# ESP32.net
KiCad netlist of a schematic drawn in Altium Designer
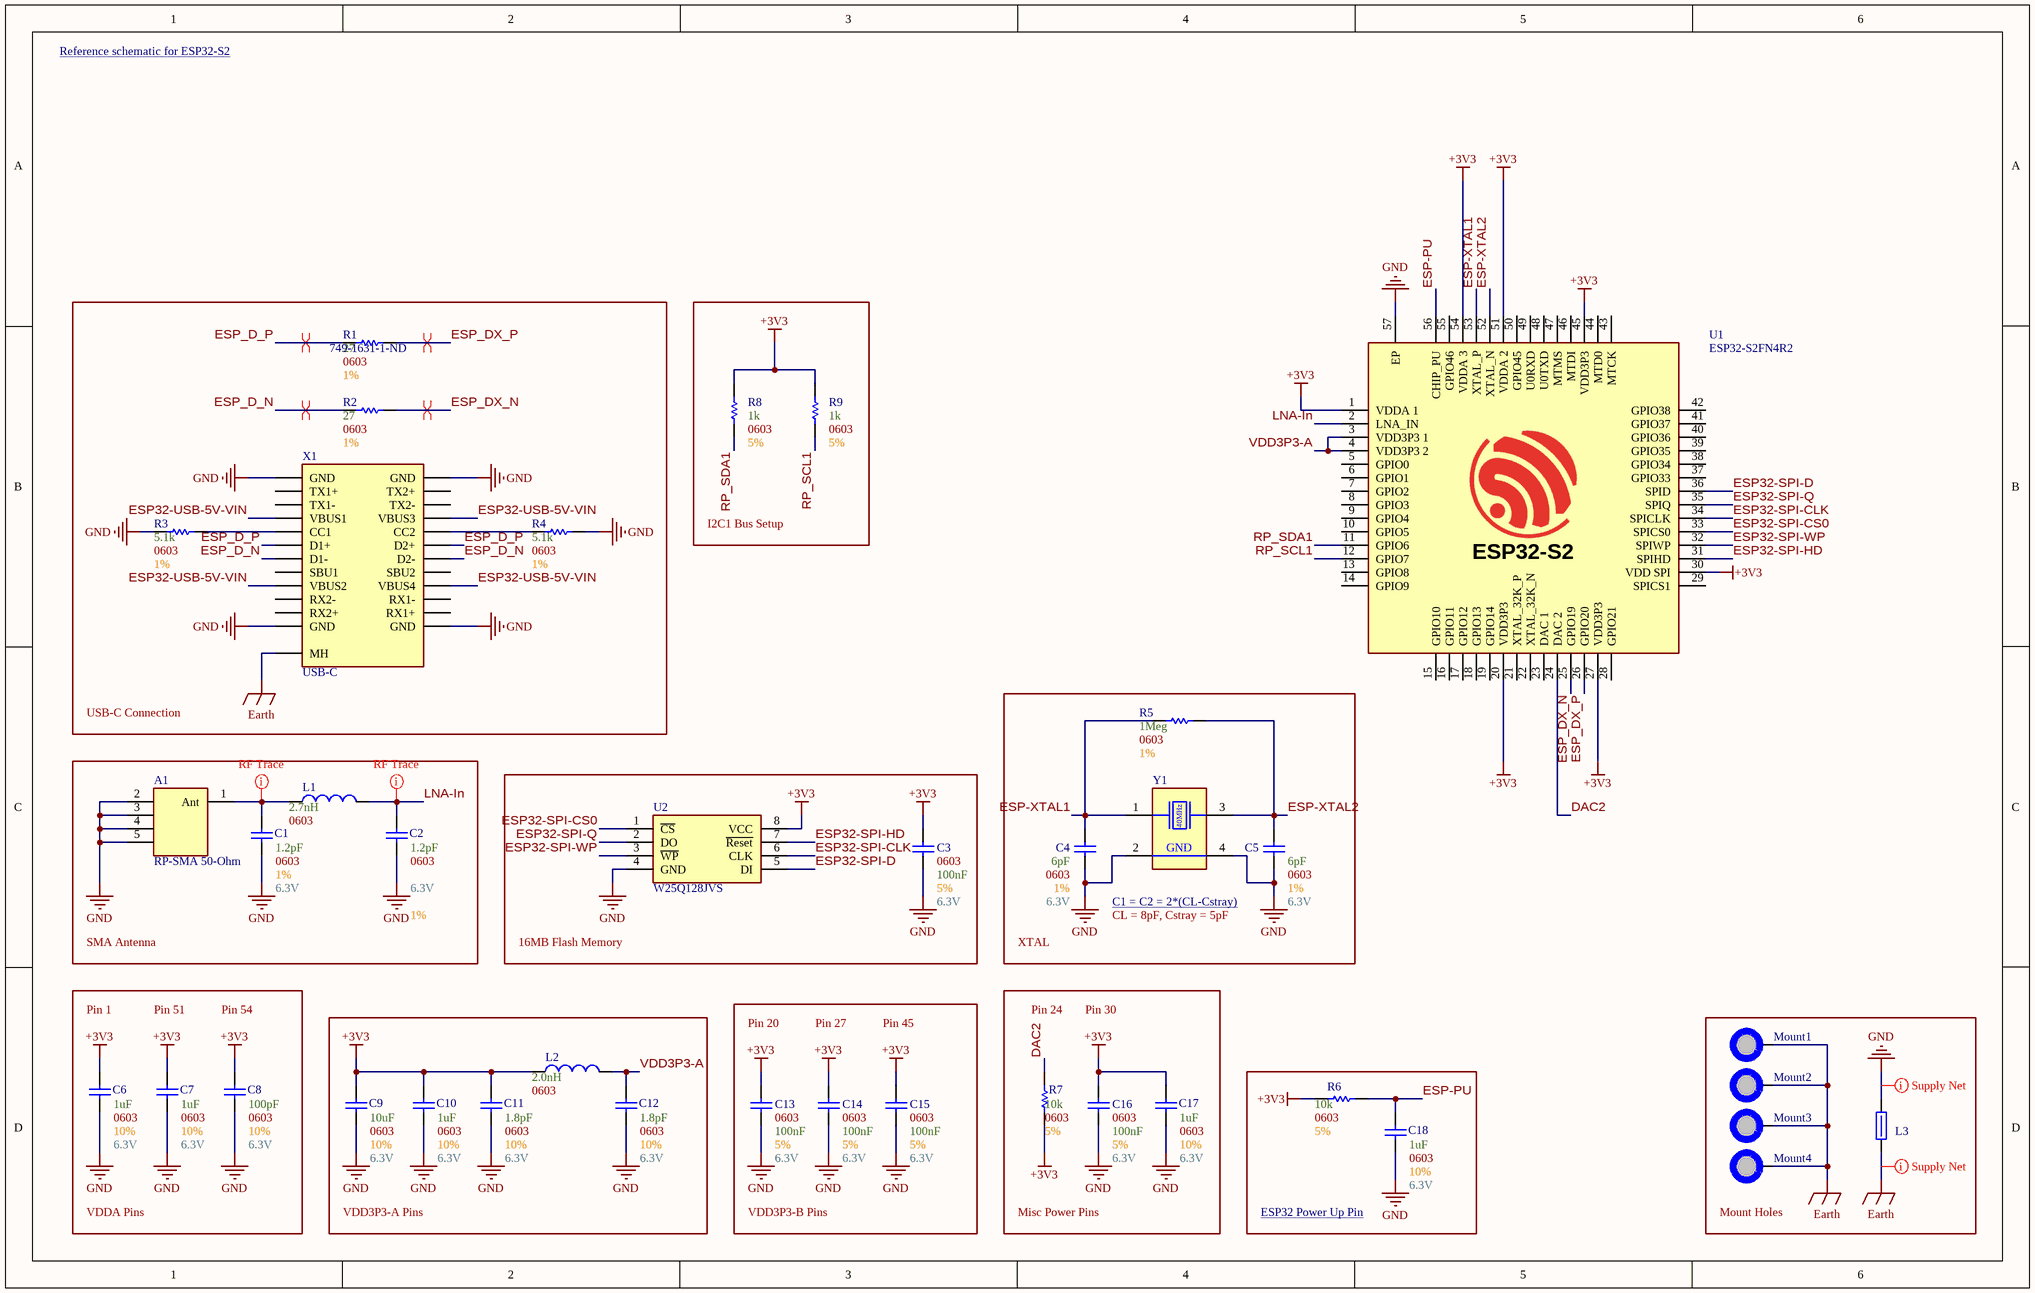
[diagram p0: ESP32.SchDoc]

(export (version "E")
  (design (tool "Eeschema 10.0.6"))
  (components
    (comp (ref "A1")
      (value "RP-SMA 50-Ohm")
      (footprint "[SMA] RP-SMA 90deg Jack")
      (description "PCB.RPSMAFRA.HT")
      (libsource (lib "RADM Connectors") (part "[SMA] RP-SMA 90deg Jack"))
    )
    (comp (ref "C1")
      (value "SMD Nonpolarized")
      (footprint "[Cap] SMD 0603")
      (fields
        (field (name "VOLTAGE") "6.3V")
        (field (name "TOLERANCE") "1%")
        (field (name "SIZE PACKAGE") "0603")
        (field (name "CAPACITANCE") "1.2pF")
      )
      (libsource (lib "RADM Components") (part "[Cap] SMD Nonpolarized"))
    )
    (comp (ref "C2")
      (value "SMD Nonpolarized")
      (footprint "[Cap] SMD 0603")
      (fields
        (field (name "VOLTAGE") "6.3V")
        (field (name "TOLERANCE") "1%")
        (field (name "SIZE PACKAGE") "0603")
        (field (name "CAPACITANCE") "1.2pF")
      )
      (libsource (lib "RADM Components") (part "[Cap] SMD Nonpolarized"))
    )
    (comp (ref "C3")
      (value "[Cap] SMD Nonpolarized")
      (footprint "[Cap] SMD 0603")
      (fields
        (field (name "SIZE PACKAGE") "0603")
        (field (name "CAPACITANCE") "100nF")
        (field (name "VOLTAGE") "6.3V")
        (field (name "TOLERANCE") "5%")
      )
      (libsource (lib "RADM Components") (part "[Cap] SMD Nonpolarized"))
    )
    (comp (ref "C4")
      (value "SMD Nonpolarized")
      (footprint "[Cap] SMD 0603")
      (fields
        (field (name "VOLTAGE") "6.3V")
        (field (name "TOLERANCE") "1%")
        (field (name "SIZE PACKAGE") "0603")
        (field (name "CAPACITANCE") "6pF")
      )
      (libsource (lib "RADM Components") (part "[Cap] SMD Nonpolarized"))
    )
    (comp (ref "C5")
      (value "SMD Nonpolarized")
      (footprint "[Cap] SMD 0603")
      (fields
        (field (name "VOLTAGE") "6.3V")
        (field (name "TOLERANCE") "1%")
        (field (name "SIZE PACKAGE") "0603")
        (field (name "CAPACITANCE") "6pF")
      )
      (libsource (lib "RADM Components") (part "[Cap] SMD Nonpolarized"))
    )
    (comp (ref "C6")
      (value "SMD Nonpolarized")
      (footprint "[Cap] SMD 0603")
      (fields
        (field (name "VOLTAGE") "6.3V")
        (field (name "TOLERANCE") "10%")
        (field (name "SIZE PACKAGE") "0603")
        (field (name "CAPACITANCE") "1uF")
      )
      (libsource (lib "RADM Components") (part "[Cap] SMD Nonpolarized"))
    )
    (comp (ref "C7")
      (value "SMD Nonpolarized")
      (footprint "[Cap] SMD 0603")
      (fields
        (field (name "VOLTAGE") "6.3V")
        (field (name "TOLERANCE") "10%")
        (field (name "SIZE PACKAGE") "0603")
        (field (name "CAPACITANCE") "1uF")
      )
      (libsource (lib "RADM Components") (part "[Cap] SMD Nonpolarized"))
    )
    (comp (ref "C8")
      (value "SMD Nonpolarized")
      (footprint "[Cap] SMD 0603")
      (fields
        (field (name "VOLTAGE") "6.3V")
        (field (name "TOLERANCE") "10%")
        (field (name "SIZE PACKAGE") "0603")
        (field (name "CAPACITANCE") "100pF")
      )
      (libsource (lib "RADM Components") (part "[Cap] SMD Nonpolarized"))
    )
    (comp (ref "C9")
      (value "SMD Nonpolarized")
      (footprint "[Cap] SMD 0603")
      (fields
        (field (name "VOLTAGE") "6.3V")
        (field (name "TOLERANCE") "10%")
        (field (name "SIZE PACKAGE") "0603")
        (field (name "CAPACITANCE") "10uF")
      )
      (libsource (lib "RADM Components") (part "[Cap] SMD Nonpolarized"))
    )
    (comp (ref "C10")
      (value "SMD Nonpolarized")
      (footprint "[Cap] SMD 0603")
      (fields
        (field (name "VOLTAGE") "6.3V")
        (field (name "TOLERANCE") "10%")
        (field (name "SIZE PACKAGE") "0603")
        (field (name "CAPACITANCE") "1uF")
      )
      (libsource (lib "RADM Components") (part "[Cap] SMD Nonpolarized"))
    )
    (comp (ref "C11")
      (value "SMD Nonpolarized")
      (footprint "[Cap] SMD 0603")
      (fields
        (field (name "VOLTAGE") "6.3V")
        (field (name "TOLERANCE") "10%")
        (field (name "SIZE PACKAGE") "0603")
        (field (name "CAPACITANCE") "1.8pF")
      )
      (libsource (lib "RADM Components") (part "[Cap] SMD Nonpolarized"))
    )
    (comp (ref "C12")
      (value "SMD Nonpolarized")
      (footprint "[Cap] SMD 0603")
      (fields
        (field (name "VOLTAGE") "6.3V")
        (field (name "TOLERANCE") "10%")
        (field (name "SIZE PACKAGE") "0603")
        (field (name "CAPACITANCE") "1.8pF")
      )
      (libsource (lib "RADM Components") (part "[Cap] SMD Nonpolarized"))
    )
    (comp (ref "C13")
      (value "[Cap] SMD Nonpolarized")
      (footprint "[Cap] SMD 0603")
      (fields
        (field (name "SIZE PACKAGE") "0603")
        (field (name "CAPACITANCE") "100nF")
        (field (name "VOLTAGE") "6.3V")
        (field (name "TOLERANCE") "5%")
      )
      (libsource (lib "RADM Components") (part "[Cap] SMD Nonpolarized"))
    )
    (comp (ref "C14")
      (value "[Cap] SMD Nonpolarized")
      (footprint "[Cap] SMD 0603")
      (fields
        (field (name "SIZE PACKAGE") "0603")
        (field (name "CAPACITANCE") "100nF")
        (field (name "VOLTAGE") "6.3V")
        (field (name "TOLERANCE") "5%")
      )
      (libsource (lib "RADM Components") (part "[Cap] SMD Nonpolarized"))
    )
    (comp (ref "C15")
      (value "[Cap] SMD Nonpolarized")
      (footprint "[Cap] SMD 0603")
      (fields
        (field (name "SIZE PACKAGE") "0603")
        (field (name "CAPACITANCE") "100nF")
        (field (name "VOLTAGE") "6.3V")
        (field (name "TOLERANCE") "5%")
      )
      (libsource (lib "RADM Components") (part "[Cap] SMD Nonpolarized"))
    )
    (comp (ref "C16")
      (value "[Cap] SMD Nonpolarized")
      (footprint "[Cap] SMD 0603")
      (fields
        (field (name "SIZE PACKAGE") "0603")
        (field (name "CAPACITANCE") "100nF")
        (field (name "VOLTAGE") "6.3V")
        (field (name "TOLERANCE") "5%")
      )
      (libsource (lib "RADM Components") (part "[Cap] SMD Nonpolarized"))
    )
    (comp (ref "C17")
      (value "SMD Nonpolarized")
      (footprint "[Cap] SMD 0603")
      (fields
        (field (name "VOLTAGE") "6.3V")
        (field (name "TOLERANCE") "10%")
        (field (name "SIZE PACKAGE") "0603")
        (field (name "CAPACITANCE") "1uF")
      )
      (libsource (lib "RADM Components") (part "[Cap] SMD Nonpolarized"))
    )
    (comp (ref "C18")
      (value "SMD Nonpolarized")
      (footprint "[Cap] SMD 0603")
      (fields
        (field (name "VOLTAGE") "6.3V")
        (field (name "TOLERANCE") "10%")
        (field (name "SIZE PACKAGE") "0603")
        (field (name "CAPACITANCE") "1uF")
      )
      (libsource (lib "RADM Components") (part "[Cap] SMD Nonpolarized"))
    )
    (comp (ref "L1")
      (value "SMD Inductor")
      (footprint "[Inductor] SMD 0603")
      (fields (field (name "SIZE PACKAGE") "0603") (field (name "INDUCTANCE") "2.7nH"))
      (libsource (lib "RADM Components") (part "[Inductor] SMD Inductor"))
    )
    (comp (ref "L2")
      (value "SMD Inductor")
      (footprint "[Inductor] SMD 0603")
      (fields (field (name "SIZE PACKAGE") "0603") (field (name "INDUCTANCE") "2.0nH"))
      (libsource (lib "RADM Components") (part "[Inductor] SMD Inductor"))
    )
    (comp (ref "L3")
      (value "652-MH2029-300Y")
      (footprint "[Ferrite] SMD Bead 0805 (1)")
      (libsource (lib "RADM Components") (part "[Ferrite] SMD Ferrite Bead (1)"))
    )
    (comp (ref "Mount1")
      (value "M3 Mount Hole")
      (footprint "[Mount] M3 Mount Hole")
      (description "Place at least 4.5mm from board edge. Plated.")
      (libsource (lib "RADM Connectors") (part "[Mount] M3 Mount Hole"))
    )
    (comp (ref "Mount2")
      (value "M3 Mount Hole")
      (footprint "[Mount] M3 Mount Hole")
      (description "Place at least 4.5mm from board edge. Plated.")
      (libsource (lib "RADM Connectors") (part "[Mount] M3 Mount Hole"))
    )
    (comp (ref "Mount3")
      (value "M3 Mount Hole")
      (footprint "[Mount] M3 Mount Hole")
      (description "Place at least 4.5mm from board edge. Plated.")
      (libsource (lib "RADM Connectors") (part "[Mount] M3 Mount Hole"))
    )
    (comp (ref "Mount4")
      (value "M3 Mount Hole")
      (footprint "[Mount] M3 Mount Hole")
      (description "Place at least 4.5mm from board edge. Plated.")
      (libsource (lib "RADM Connectors") (part "[Mount] M3 Mount Hole"))
    )
    (comp (ref "R1")
      (value "[Res] SMD Resistor")
      (footprint "[Res] SMD 0603")
      (description "Generic")
      (fields
        (field (name "TOLERANCE") "1%")
        (field (name "RESISTANCE") "27")
        (field (name "SIZE PACKAGE") "0603")
        (field (name "SUPPLIER PART NUMBER 1") "749-1631-1-ND")
      )
      (libsource (lib "RADM Components") (part "[Res] SMD Resistor"))
    )
    (comp (ref "R2")
      (value "[Res] SMD Resistor")
      (footprint "[Res] SMD 0603")
      (description "Generic")
      (fields
        (field (name "TOLERANCE") "1%")
        (field (name "RESISTANCE") "27")
        (field (name "SIZE PACKAGE") "0603")
      )
      (libsource (lib "RADM Components") (part "[Res] SMD Resistor"))
    )
    (comp (ref "R3")
      (value "[Res] SMD Resistor")
      (footprint "[Res] SMD 0603")
      (description "Generic")
      (fields
        (field (name "TOLERANCE") "1%")
        (field (name "RESISTANCE") "5.1k")
        (field (name "SIZE PACKAGE") "0603")
      )
      (libsource (lib "RADM Components") (part "[Res] SMD Resistor"))
    )
    (comp (ref "R4")
      (value "[Res] SMD Resistor")
      (footprint "[Res] SMD 0603")
      (description "Generic")
      (fields
        (field (name "TOLERANCE") "1%")
        (field (name "RESISTANCE") "5.1k")
        (field (name "SIZE PACKAGE") "0603")
      )
      (libsource (lib "RADM Components") (part "[Res] SMD Resistor"))
    )
    (comp (ref "R5")
      (value "[Res] SMD Resistor")
      (footprint "[Res] SMD 0603")
      (description "Generic")
      (fields
        (field (name "TOLERANCE") "1%")
        (field (name "RESISTANCE") "1Meg")
        (field (name "SIZE PACKAGE") "0603")
      )
      (libsource (lib "RADM Components") (part "[Res] SMD Resistor"))
    )
    (comp (ref "R6")
      (value "[Res] SMD Resistor")
      (footprint "[Res] SMD 0603")
      (description "Generic")
      (fields
        (field (name "TOLERANCE") "5%")
        (field (name "RESISTANCE") "10k")
        (field (name "SIZE PACKAGE") "0603")
      )
      (libsource (lib "RADM Components") (part "[Res] SMD Resistor"))
    )
    (comp (ref "R7")
      (value "[Res] SMD Resistor")
      (footprint "[Res] SMD 0603")
      (description "Generic")
      (fields
        (field (name "TOLERANCE") "5%")
        (field (name "RESISTANCE") "10k")
        (field (name "SIZE PACKAGE") "0603")
      )
      (libsource (lib "RADM Components") (part "[Res] SMD Resistor"))
    )
    (comp (ref "R8")
      (value "[Res] SMD Resistor")
      (footprint "[Res] SMD 0603")
      (description "Generic")
      (fields
        (field (name "RESISTANCE") "1k")
        (field (name "SIZE PACKAGE") "0603")
        (field (name "TOLERANCE") "5%")
      )
      (libsource (lib "RADM Components") (part "[Res] SMD Resistor"))
    )
    (comp (ref "R9")
      (value "[Res] SMD Resistor")
      (footprint "[Res] SMD 0603")
      (description "Generic")
      (fields
        (field (name "RESISTANCE") "1k")
        (field (name "SIZE PACKAGE") "0603")
        (field (name "TOLERANCE") "5%")
      )
      (libsource (lib "RADM Components") (part "[Res] SMD Resistor"))
    )
    (comp (ref "U1")
      (value "ESP32-S2FN4R2")
      (footprint "[MCU] ESP32-S2")
      (libsource (lib "RADM Components") (part "[MCU] ESP32-S2"))
    )
    (comp (ref "U2")
      (value "W25Q128JVS")
      (footprint "[Mem] 16Mb Flash Memory")
      (description "W25Q128JVSIQ TR")
      (libsource (lib "RADM Components") (part "[Mem] 16Mb Flash Memory"))
    )
    (comp (ref "X1")
      (value "USB-C")
      (footprint "[Port] USB-C")
      (libsource (lib "RADM Connectors") (part "[Port] USB Type-C"))
    )
    (comp (ref "Y1")
      (value "40MHz Crystal")
      (footprint "[XTAL] SMD 40MHz")
      (description "CX2016DB40000D0FLJCC")
      (libsource (lib "RADM Components") (part "[XTAL] SMD 40MHz"))
    )
  )
  (nets
    (net (code "1") (name "+3V3") (class "Default")
      (node (ref "C10") (pin "2") (pinfunction "2_2") (pintype "passive"))
      (node (ref "C11") (pin "2") (pinfunction "2_2") (pintype "passive"))
      (node (ref "C13") (pin "2") (pinfunction "2_2") (pintype "passive"))
      (node (ref "C14") (pin "2") (pinfunction "2_2") (pintype "passive"))
      (node (ref "C15") (pin "2") (pinfunction "2_2") (pintype "passive"))
      (node (ref "C16") (pin "2") (pinfunction "2_2") (pintype "passive"))
      (node (ref "C17") (pin "2") (pinfunction "2_2") (pintype "passive"))
      (node (ref "C3") (pin "2") (pinfunction "2_2") (pintype "passive"))
      (node (ref "C6") (pin "2") (pinfunction "2_2") (pintype "passive"))
      (node (ref "C7") (pin "2") (pinfunction "2_2") (pintype "passive"))
      (node (ref "C8") (pin "2") (pinfunction "2_2") (pintype "passive"))
      (node (ref "C9") (pin "2") (pinfunction "2_2") (pintype "passive"))
      (node (ref "L2") (pin "1") (pinfunction "1_1") (pintype "passive"))
      (node (ref "R6") (pin "1") (pinfunction "1_1") (pintype "passive"))
      (node (ref "R7") (pin "1") (pinfunction "1_1") (pintype "passive"))
      (node (ref "R8") (pin "2") (pinfunction "2_2") (pintype "passive"))
      (node (ref "R9") (pin "2") (pinfunction "2_2") (pintype "passive"))
      (node (ref "U1") (pin "1") (pinfunction "VDDA_1_1") (pintype "passive"))
      (node (ref "U1") (pin "20") (pinfunction "VDD3P3_20") (pintype "passive"))
      (node (ref "U1") (pin "27") (pinfunction "VDD3P3_27") (pintype "passive"))
      (node (ref "U1") (pin "30") (pinfunction "VDD_SPI_30") (pintype "passive"))
      (node (ref "U1") (pin "45") (pinfunction "VDD3P3_45") (pintype "passive"))
      (node (ref "U1") (pin "51") (pinfunction "VDDA_2_51") (pintype "passive"))
      (node (ref "U1") (pin "54") (pinfunction "VDDA_3_54") (pintype "passive"))
      (node (ref "U2") (pin "8") (pinfunction "VCC_8") (pintype "passive"))
    )
    (net (code "2") (name "/DAC2") (class "Default")
      (node (ref "R7") (pin "2") (pinfunction "2_2") (pintype "passive"))
      (node (ref "U1") (pin "24") (pinfunction "DAC_2_24") (pintype "passive"))
    )
    (net (code "3") (name "/ESP-PU") (class "Default")
      (node (ref "C18") (pin "2") (pinfunction "2_2") (pintype "passive"))
      (node (ref "R6") (pin "2") (pinfunction "2_2") (pintype "passive"))
      (node (ref "U1") (pin "56") (pinfunction "CHIP_PU_56") (pintype "passive"))
    )
    (net (code "4") (name "/ESP-XTAL1") (class "Default")
      (node (ref "C4") (pin "2") (pinfunction "2_2") (pintype "passive"))
      (node (ref "R5") (pin "2") (pinfunction "2_2") (pintype "passive"))
      (node (ref "U1") (pin "53") (pinfunction "XTAL_P_53") (pintype "passive"))
      (node (ref "Y1") (pin "1") (pinfunction "XTAL1_1") (pintype "power_in"))
    )
    (net (code "5") (name "/ESP-XTAL2") (class "Default")
      (node (ref "C5") (pin "2") (pinfunction "2_2") (pintype "passive"))
      (node (ref "R5") (pin "1") (pinfunction "1_1") (pintype "passive"))
      (node (ref "U1") (pin "52") (pinfunction "XTAL_N_52") (pintype "passive"))
      (node (ref "Y1") (pin "3") (pinfunction "XTAL2_3") (pintype "power_in"))
    )
    (net (code "6") (name "/ESP32-SPI-CLK") (class "Default")
      (node (ref "U1") (pin "34") (pinfunction "SPICLK_34") (pintype "passive"))
      (node (ref "U2") (pin "6") (pinfunction "CLK_6") (pintype "passive"))
    )
    (net (code "7") (name "/ESP32-SPI-CS0") (class "Default")
      (node (ref "U1") (pin "33") (pinfunction "SPICS0_33") (pintype "passive"))
      (node (ref "U2") (pin "1") (pinfunction "~{CS}_1") (pintype "passive"))
    )
    (net (code "8") (name "/ESP32-SPI-D") (class "Default")
      (node (ref "U1") (pin "36") (pinfunction "SPID_36") (pintype "passive"))
      (node (ref "U2") (pin "5") (pinfunction "DI_5") (pintype "passive"))
    )
    (net (code "9") (name "/ESP32-SPI-HD") (class "Default")
      (node (ref "U1") (pin "31") (pinfunction "SPIHD_31") (pintype "passive"))
      (node (ref "U2") (pin "7") (pinfunction "~{Reset}_7") (pintype "passive"))
    )
    (net (code "10") (name "/ESP32-SPI-Q") (class "Default")
      (node (ref "U1") (pin "35") (pinfunction "SPIQ_35") (pintype "passive"))
      (node (ref "U2") (pin "2") (pinfunction "DO_2") (pintype "passive"))
    )
    (net (code "11") (name "/ESP32-SPI-WP") (class "Default")
      (node (ref "U1") (pin "32") (pinfunction "SPIWP_32") (pintype "passive"))
      (node (ref "U2") (pin "3") (pinfunction "~{WP}_3") (pintype "passive"))
    )
    (net (code "12") (name "/ESP32-USB-5V-VIN") (class "Default")
      (node (ref "X1") (pin "A4") (pinfunction "VBUS1_A4") (pintype "passive"))
      (node (ref "X1") (pin "A9") (pinfunction "VBUS2_A9") (pintype "passive"))
      (node (ref "X1") (pin "B4") (pinfunction "VBUS3_B4") (pintype "passive"))
      (node (ref "X1") (pin "B9") (pinfunction "VBUS4_B9") (pintype "passive"))
    )
    (net (code "13") (name "/ESP_DX_N") (class "Default")
      (node (ref "R2") (pin "2") (pinfunction "2_2") (pintype "passive"))
      (node (ref "U1") (pin "25") (pinfunction "GPIO19_25") (pintype "passive"))
    )
    (net (code "14") (name "/ESP_DX_P") (class "Default")
      (node (ref "R1") (pin "2") (pinfunction "2_2") (pintype "passive"))
      (node (ref "U1") (pin "26") (pinfunction "GPIO20_26") (pintype "passive"))
    )
    (net (code "15") (name "/ESP_D_N") (class "Default")
      (node (ref "R2") (pin "1") (pinfunction "1_1") (pintype "passive"))
      (node (ref "X1") (pin "A7") (pinfunction "D1-_A7") (pintype "passive"))
      (node (ref "X1") (pin "B7") (pinfunction "D2-_B7") (pintype "passive"))
    )
    (net (code "16") (name "/ESP_D_P") (class "Default")
      (node (ref "R1") (pin "1") (pinfunction "1_1") (pintype "passive"))
      (node (ref "X1") (pin "A6") (pinfunction "D1+_A6") (pintype "passive"))
      (node (ref "X1") (pin "B6") (pinfunction "D2+_B6") (pintype "passive"))
    )
    (net (code "17") (name "/LNA-In") (class "Default")
      (node (ref "C2") (pin "2") (pinfunction "2_2") (pintype "passive"))
      (node (ref "L1") (pin "2") (pinfunction "2_2") (pintype "passive"))
      (node (ref "U1") (pin "2") (pinfunction "LNA_IN_2") (pintype "passive"))
    )
    (net (code "18") (name "/RP_SCL1") (class "Default")
      (node (ref "R9") (pin "1") (pinfunction "1_1") (pintype "passive"))
      (node (ref "U1") (pin "12") (pinfunction "GPIO7_12") (pintype "passive"))
    )
    (net (code "19") (name "/RP_SDA1") (class "Default")
      (node (ref "R8") (pin "1") (pinfunction "1_1") (pintype "passive"))
      (node (ref "U1") (pin "11") (pinfunction "GPIO6_11") (pintype "passive"))
    )
    (net (code "20") (name "/VDD3P3-A") (class "Default")
      (node (ref "C12") (pin "2") (pinfunction "2_2") (pintype "passive"))
      (node (ref "L2") (pin "2") (pinfunction "2_2") (pintype "passive"))
      (node (ref "U1") (pin "3") (pinfunction "VDD3P3_1_3") (pintype "passive"))
      (node (ref "U1") (pin "4") (pinfunction "VDD3P3_2_4") (pintype "passive"))
    )
    (net (code "21") (name "Earth") (class "Default")
      (node (ref "L3") (pin "1") (pinfunction "1_1") (pintype "passive"))
      (node (ref "Mount1") (pin "1") (pintype "power_in"))
      (node (ref "Mount2") (pin "1") (pintype "power_in"))
      (node (ref "Mount3") (pin "1") (pintype "power_in"))
      (node (ref "Mount4") (pin "1") (pintype "power_in"))
      (node (ref "X1") (pin "MH") (pinfunction "MH_MH") (pintype "passive"))
    )
    (net (code "22") (name "GND") (class "Default")
      (node (ref "A1") (pin "2") (pinfunction "2_2") (pintype "passive"))
      (node (ref "A1") (pin "3") (pinfunction "3_3") (pintype "passive"))
      (node (ref "A1") (pin "4") (pinfunction "4_4") (pintype "passive"))
      (node (ref "A1") (pin "5") (pinfunction "5_5") (pintype "passive"))
      (node (ref "C1") (pin "1") (pinfunction "1_1") (pintype "passive"))
      (node (ref "C10") (pin "1") (pinfunction "1_1") (pintype "passive"))
      (node (ref "C11") (pin "1") (pinfunction "1_1") (pintype "passive"))
      (node (ref "C12") (pin "1") (pinfunction "1_1") (pintype "passive"))
      (node (ref "C13") (pin "1") (pinfunction "1_1") (pintype "passive"))
      (node (ref "C14") (pin "1") (pinfunction "1_1") (pintype "passive"))
      (node (ref "C15") (pin "1") (pinfunction "1_1") (pintype "passive"))
      (node (ref "C16") (pin "1") (pinfunction "1_1") (pintype "passive"))
      (node (ref "C17") (pin "1") (pinfunction "1_1") (pintype "passive"))
      (node (ref "C18") (pin "1") (pinfunction "1_1") (pintype "passive"))
      (node (ref "C2") (pin "1") (pinfunction "1_1") (pintype "passive"))
      (node (ref "C3") (pin "1") (pinfunction "1_1") (pintype "passive"))
      (node (ref "C4") (pin "1") (pinfunction "1_1") (pintype "passive"))
      (node (ref "C5") (pin "1") (pinfunction "1_1") (pintype "passive"))
      (node (ref "C6") (pin "1") (pinfunction "1_1") (pintype "passive"))
      (node (ref "C7") (pin "1") (pinfunction "1_1") (pintype "passive"))
      (node (ref "C8") (pin "1") (pinfunction "1_1") (pintype "passive"))
      (node (ref "C9") (pin "1") (pinfunction "1_1") (pintype "passive"))
      (node (ref "L3") (pin "2") (pinfunction "2_2") (pintype "passive"))
      (node (ref "R3") (pin "1") (pinfunction "1_1") (pintype "passive"))
      (node (ref "R4") (pin "2") (pinfunction "2_2") (pintype "passive"))
      (node (ref "U1") (pin "57") (pinfunction "EP_57") (pintype "passive"))
      (node (ref "U2") (pin "4") (pinfunction "GND_4") (pintype "passive"))
      (node (ref "X1") (pin "A1") (pinfunction "GND_A1") (pintype "passive"))
      (node (ref "X1") (pin "A12") (pinfunction "GND_A12") (pintype "passive"))
      (node (ref "X1") (pin "B1") (pinfunction "GND_B1") (pintype "passive"))
      (node (ref "X1") (pin "B12") (pinfunction "GND_B12") (pintype "passive"))
      (node (ref "Y1") (pin "2") (pinfunction "GND_2") (pintype "power_in"))
      (node (ref "Y1") (pin "4") (pinfunction "GND_4") (pintype "power_in"))
    )
    (net (code "23") (name "Net-(A1-Ant)") (class "Default")
      (node (ref "A1") (pin "1") (pinfunction "Ant_1") (pintype "passive"))
      (node (ref "C1") (pin "2") (pinfunction "2_2") (pintype "passive"))
      (node (ref "L1") (pin "1") (pinfunction "1_1") (pintype "passive"))
    )
    (net (code "24") (name "Net-(X1-CC1)") (class "Default")
      (node (ref "R3") (pin "2") (pinfunction "2_2") (pintype "passive"))
      (node (ref "X1") (pin "A5") (pinfunction "CC1_A5") (pintype "passive"))
    )
    (net (code "25") (name "Net-(X1-CC2)") (class "Default")
      (node (ref "R4") (pin "1") (pinfunction "1_1") (pintype "passive"))
      (node (ref "X1") (pin "B5") (pinfunction "CC2_B5") (pintype "passive"))
    )
    (net (code "26") (name "unconnected-(U1-DAC_1-Pad23)") (class "Default")
      (node (ref "U1") (pin "23") (pinfunction "DAC_1_23") (pintype "passive"))
    )
    (net (code "27") (name "unconnected-(U1-GPIO0-Pad5)") (class "Default")
      (node (ref "U1") (pin "5") (pinfunction "GPIO0_5") (pintype "passive"))
    )
    (net (code "28") (name "unconnected-(U1-GPIO1-Pad6)") (class "Default")
      (node (ref "U1") (pin "6") (pinfunction "GPIO1_6") (pintype "passive"))
    )
    (net (code "29") (name "unconnected-(U1-GPIO2-Pad7)") (class "Default")
      (node (ref "U1") (pin "7") (pinfunction "GPIO2_7") (pintype "passive"))
    )
    (net (code "30") (name "unconnected-(U1-GPIO3-Pad8)") (class "Default")
      (node (ref "U1") (pin "8") (pinfunction "GPIO3_8") (pintype "passive"))
    )
    (net (code "31") (name "unconnected-(U1-GPIO4-Pad9)") (class "Default")
      (node (ref "U1") (pin "9") (pinfunction "GPIO4_9") (pintype "passive"))
    )
    (net (code "32") (name "unconnected-(U1-GPIO5-Pad10)") (class "Default")
      (node (ref "U1") (pin "10") (pinfunction "GPIO5_10") (pintype "passive"))
    )
    (net (code "33") (name "unconnected-(U1-GPIO8-Pad13)") (class "Default")
      (node (ref "U1") (pin "13") (pinfunction "GPIO8_13") (pintype "passive"))
    )
    (net (code "34") (name "unconnected-(U1-GPIO9-Pad14)") (class "Default")
      (node (ref "U1") (pin "14") (pinfunction "GPIO9_14") (pintype "passive"))
    )
    (net (code "35") (name "unconnected-(U1-GPIO10-Pad15)") (class "Default")
      (node (ref "U1") (pin "15") (pinfunction "GPIO10_15") (pintype "passive"))
    )
    (net (code "36") (name "unconnected-(U1-GPIO11-Pad16)") (class "Default")
      (node (ref "U1") (pin "16") (pinfunction "GPIO11_16") (pintype "passive"))
    )
    (net (code "37") (name "unconnected-(U1-GPIO12-Pad17)") (class "Default")
      (node (ref "U1") (pin "17") (pinfunction "GPIO12_17") (pintype "passive"))
    )
    (net (code "38") (name "unconnected-(U1-GPIO13-Pad18)") (class "Default")
      (node (ref "U1") (pin "18") (pinfunction "GPIO13_18") (pintype "passive"))
    )
    (net (code "39") (name "unconnected-(U1-GPIO14-Pad19)") (class "Default")
      (node (ref "U1") (pin "19") (pinfunction "GPIO14_19") (pintype "passive"))
    )
    (net (code "40") (name "unconnected-(U1-GPIO21-Pad28)") (class "Default")
      (node (ref "U1") (pin "28") (pinfunction "GPIO21_28") (pintype "passive"))
    )
    (net (code "41") (name "unconnected-(U1-GPIO33-Pad37)") (class "Default")
      (node (ref "U1") (pin "37") (pinfunction "GPIO33_37") (pintype "passive"))
    )
    (net (code "42") (name "unconnected-(U1-GPIO34-Pad38)") (class "Default")
      (node (ref "U1") (pin "38") (pinfunction "GPIO34_38") (pintype "passive"))
    )
    (net (code "43") (name "unconnected-(U1-GPIO35-Pad39)") (class "Default")
      (node (ref "U1") (pin "39") (pinfunction "GPIO35_39") (pintype "passive"))
    )
    (net (code "44") (name "unconnected-(U1-GPIO36-Pad40)") (class "Default")
      (node (ref "U1") (pin "40") (pinfunction "GPIO36_40") (pintype "passive"))
    )
    (net (code "45") (name "unconnected-(U1-GPIO37-Pad41)") (class "Default")
      (node (ref "U1") (pin "41") (pinfunction "GPIO37_41") (pintype "passive"))
    )
    (net (code "46") (name "unconnected-(U1-GPIO38-Pad42)") (class "Default")
      (node (ref "U1") (pin "42") (pinfunction "GPIO38_42") (pintype "passive"))
    )
    (net (code "47") (name "unconnected-(U1-GPIO45-Pad50)") (class "Default")
      (node (ref "U1") (pin "50") (pinfunction "GPIO45_50") (pintype "passive"))
    )
    (net (code "48") (name "unconnected-(U1-GPIO46-Pad55)") (class "Default")
      (node (ref "U1") (pin "55") (pinfunction "GPIO46_55") (pintype "passive"))
    )
    (net (code "49") (name "unconnected-(U1-MTCK-Pad43)") (class "Default")
      (node (ref "U1") (pin "43") (pinfunction "MTCK_43") (pintype "passive"))
    )
    (net (code "50") (name "unconnected-(U1-MTD0-Pad44)") (class "Default")
      (node (ref "U1") (pin "44") (pinfunction "MTD0_44") (pintype "passive"))
    )
    (net (code "51") (name "unconnected-(U1-MTDI-Pad46)") (class "Default")
      (node (ref "U1") (pin "46") (pinfunction "MTDI_46") (pintype "passive"))
    )
    (net (code "52") (name "unconnected-(U1-MTMS-Pad47)") (class "Default")
      (node (ref "U1") (pin "47") (pinfunction "MTMS_47") (pintype "passive"))
    )
    (net (code "53") (name "unconnected-(U1-SPICS1-Pad29)") (class "Default")
      (node (ref "U1") (pin "29") (pinfunction "SPICS1_29") (pintype "passive"))
    )
    (net (code "54") (name "unconnected-(U1-U0RXD-Pad49)") (class "Default")
      (node (ref "U1") (pin "49") (pinfunction "U0RXD_49") (pintype "passive"))
    )
    (net (code "55") (name "unconnected-(U1-U0TXD-Pad48)") (class "Default")
      (node (ref "U1") (pin "48") (pinfunction "U0TXD_48") (pintype "passive"))
    )
    (net (code "56") (name "unconnected-(U1-XTAL_32K_N-Pad22)") (class "Default")
      (node (ref "U1") (pin "22") (pinfunction "XTAL_32K_N_22") (pintype "passive"))
    )
    (net (code "57") (name "unconnected-(U1-XTAL_32K_P-Pad21)") (class "Default")
      (node (ref "U1") (pin "21") (pinfunction "XTAL_32K_P_21") (pintype "passive"))
    )
    (net (code "58") (name "unconnected-(X1-RX1+-PadB11)") (class "Default")
      (node (ref "X1") (pin "B11") (pinfunction "RX1+_B11") (pintype "passive"))
    )
    (net (code "59") (name "unconnected-(X1-RX1--PadB10)") (class "Default")
      (node (ref "X1") (pin "B10") (pinfunction "RX1-_B10") (pintype "passive"))
    )
    (net (code "60") (name "unconnected-(X1-RX2+-PadA11)") (class "Default")
      (node (ref "X1") (pin "A11") (pinfunction "RX2+_A11") (pintype "passive"))
    )
    (net (code "61") (name "unconnected-(X1-RX2--PadA10)") (class "Default")
      (node (ref "X1") (pin "A10") (pinfunction "RX2-_A10") (pintype "passive"))
    )
    (net (code "62") (name "unconnected-(X1-SBU1-PadA8)") (class "Default")
      (node (ref "X1") (pin "A8") (pinfunction "SBU1_A8") (pintype "passive"))
    )
    (net (code "63") (name "unconnected-(X1-SBU2-PadB8)") (class "Default")
      (node (ref "X1") (pin "B8") (pinfunction "SBU2_B8") (pintype "passive"))
    )
    (net (code "64") (name "unconnected-(X1-TX1+-PadA2)") (class "Default")
      (node (ref "X1") (pin "A2") (pinfunction "TX1+_A2") (pintype "passive"))
    )
    (net (code "65") (name "unconnected-(X1-TX1--PadA3)") (class "Default")
      (node (ref "X1") (pin "A3") (pinfunction "TX1-_A3") (pintype "passive"))
    )
    (net (code "66") (name "unconnected-(X1-TX2+-PadB2)") (class "Default")
      (node (ref "X1") (pin "B2") (pinfunction "TX2+_B2") (pintype "passive"))
    )
    (net (code "67") (name "unconnected-(X1-TX2--PadB3)") (class "Default")
      (node (ref "X1") (pin "B3") (pinfunction "TX2-_B3") (pintype "passive"))
    )
  )
)
